# Electrolyser_demo_Dec_2025.net
KiCad netlist of a schematic drawn in EasyEDA
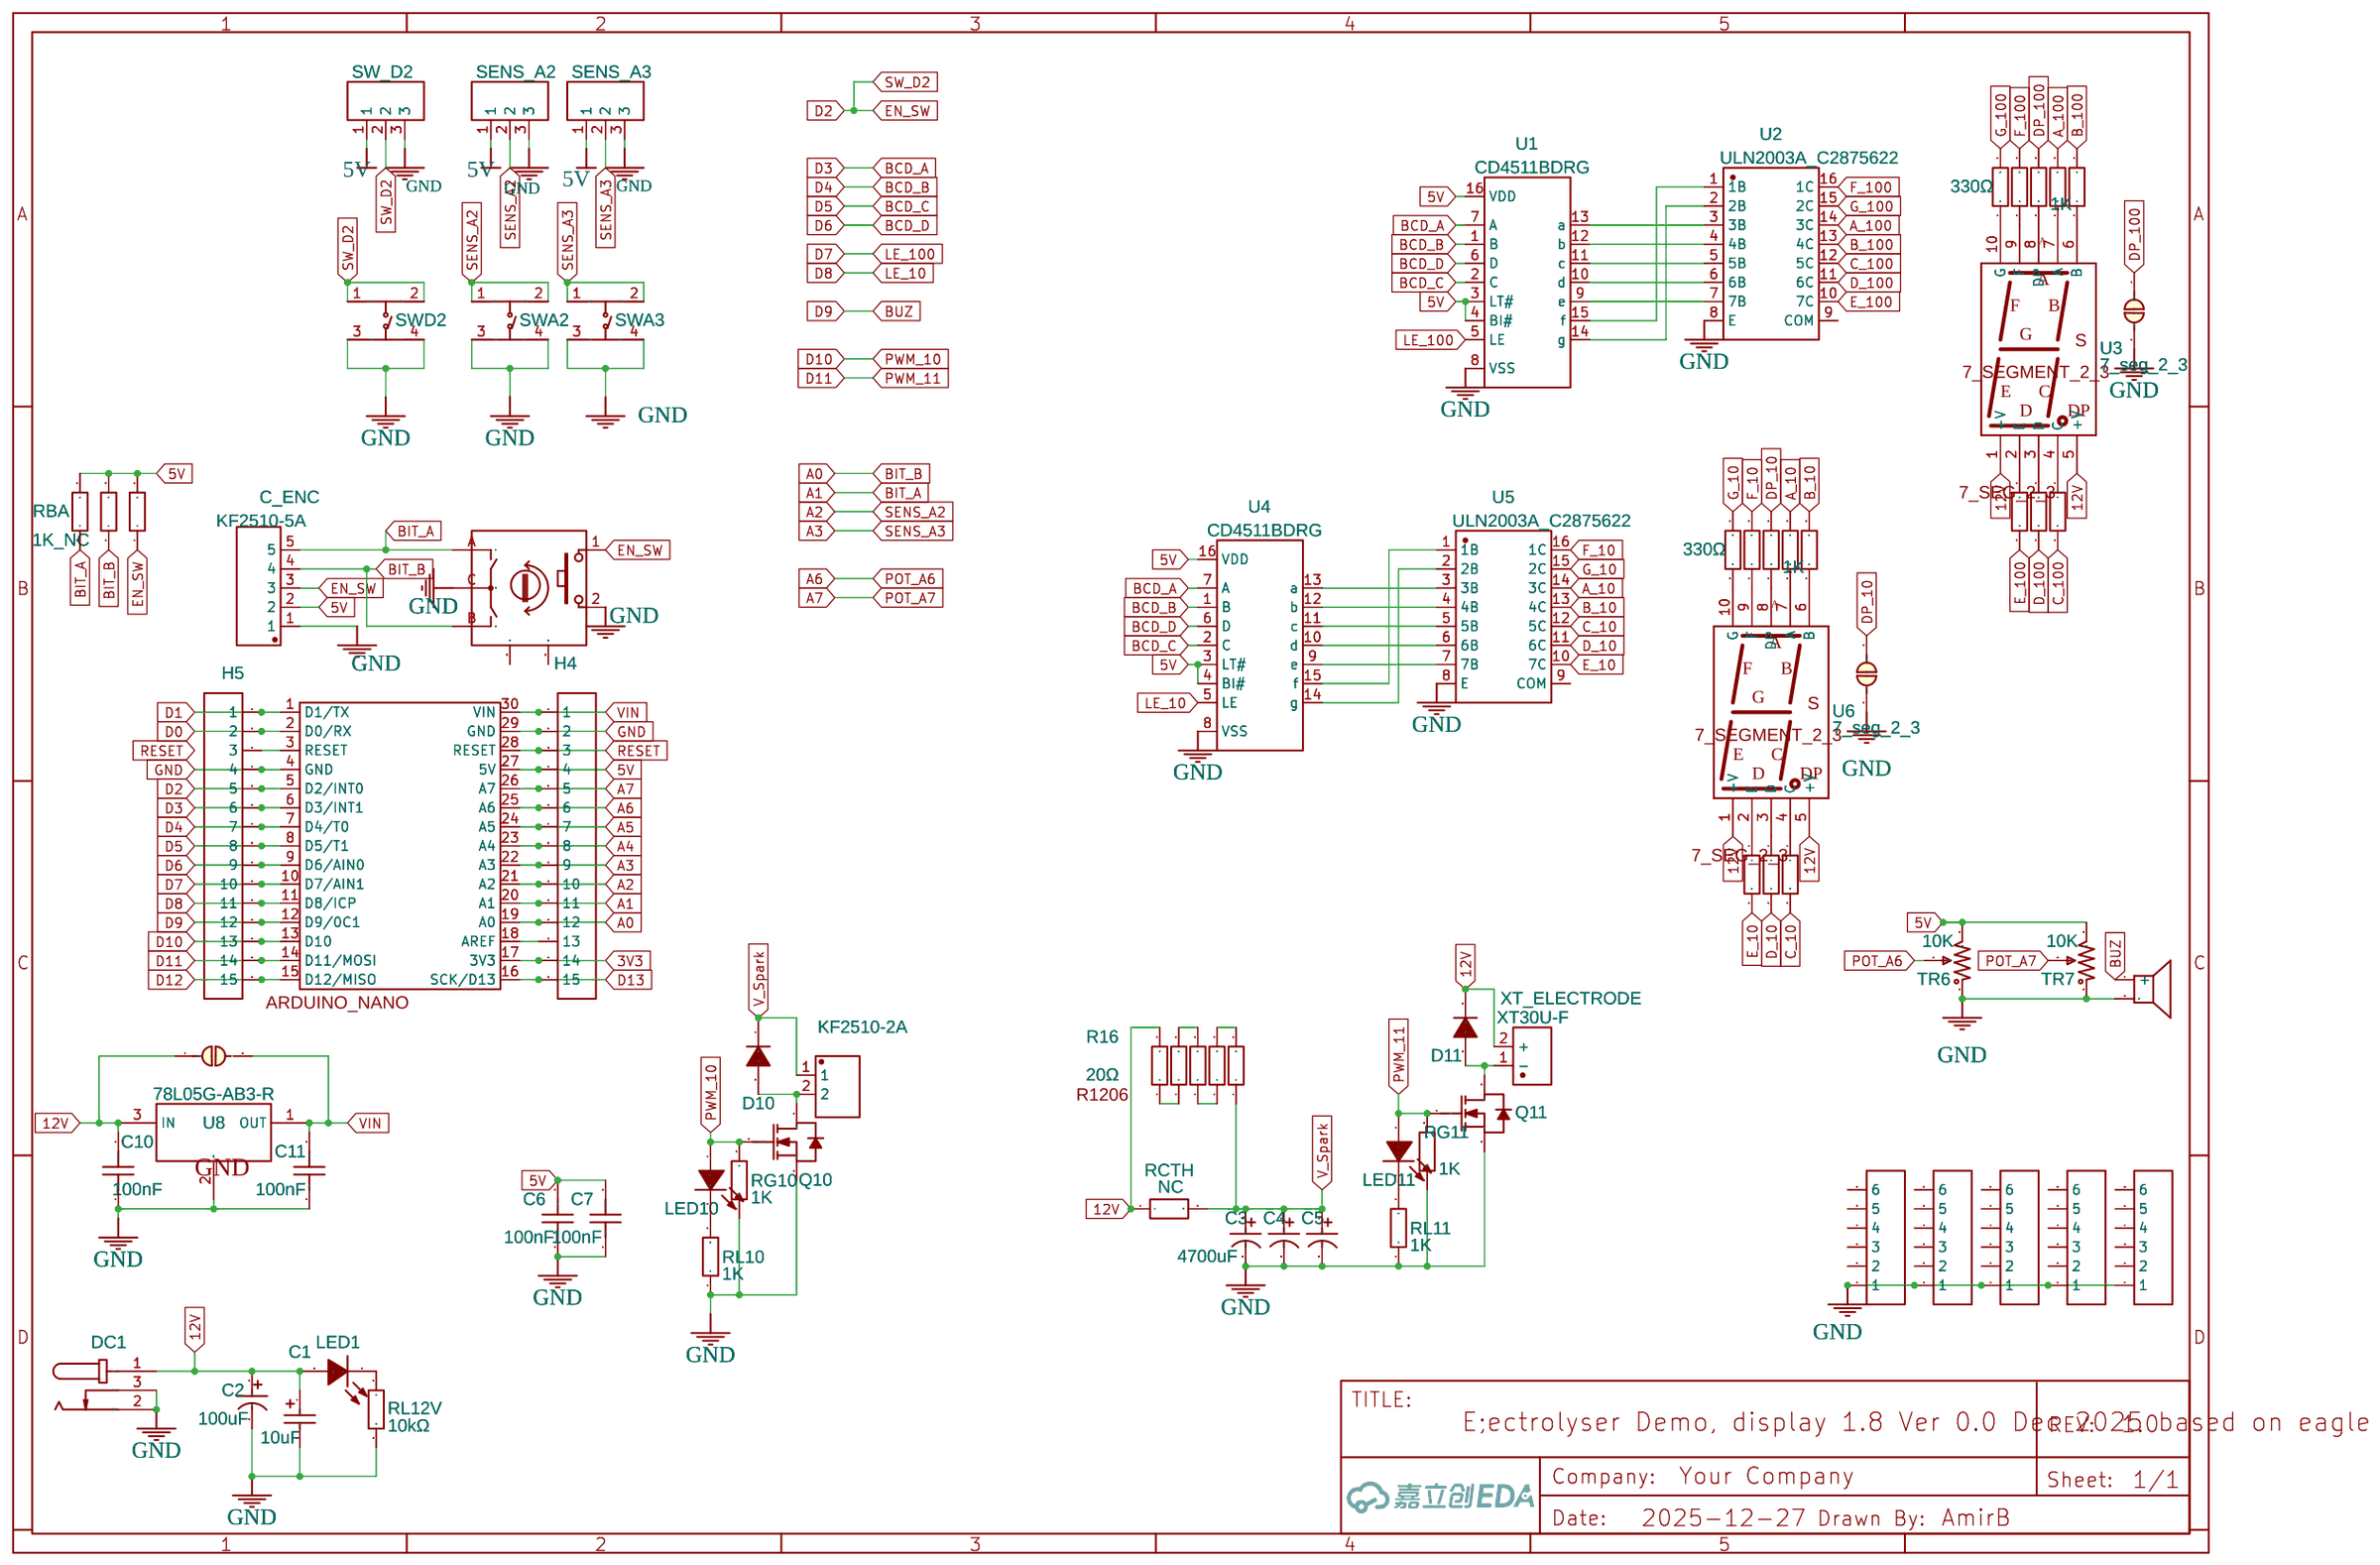
[diagram p0: schematic sheet]

(export (version "E")
  (design (tool "Eeschema 10.0.6"))
  (components
    (comp (ref "BUZZER1")
      (value "BUZZER-12X9")
      (fields (field (name "Manufacturer Part") "buzzer-12X9"))
      (libsource (lib "") (part "BUZZER-12X9"))
    )
    (comp (ref "C1")
      (value "10uF")
      (fields (field (name "Manufacturer Part") "TAJA106K016RNJ") (field (name "Manufacturer") "Kyocera AVX"))
      (libsource (lib "") (part "TAJA106K016RNJ"))
    )
    (comp (ref "C2")
      (value "100uF")
      (fields
        (field (name "Manufacturer Part") "KM107M035E11RR0VH2FP0")
        (field (name "Manufacturer") "CX(承兴)")
      )
      (libsource (lib "") (part "100uF 35V 6.3*11"))
    )
    (comp (ref "C3")
      (value "4700uF")
      (fields
        (field (name "Manufacturer Part") "KM478M025K25RR0VH2FP0")
        (field (name "Manufacturer") "Chengx(承兴)")
      )
      (libsource (lib "") (part "4700uF 25V 16*25V"))
    )
    (comp (ref "C4")
      (value "4700uF")
      (fields
        (field (name "Manufacturer Part") "KM478M025K25RR0VH2FP0")
        (field (name "Manufacturer") "Chengx(承兴)")
      )
      (libsource (lib "") (part "4700uF 25V 16*25V"))
    )
    (comp (ref "C5")
      (value "4700uF")
      (fields
        (field (name "Manufacturer Part") "KM478M025K25RR0VH2FP0")
        (field (name "Manufacturer") "Chengx(承兴)")
      )
      (libsource (lib "") (part "4700uF 25V 16*25V"))
    )
    (comp (ref "C6")
      (value "100nF")
      (fields
        (field (name "Manufacturer Part") "CC0603KRX7R9BB104")
        (field (name "Manufacturer") "YAGEO(国巨)")
      )
      (libsource (lib "") (part "CC0603KRX7R9BB104"))
    )
    (comp (ref "C7")
      (value "100nF")
      (fields
        (field (name "Manufacturer Part") "CC0603KRX7R9BB104")
        (field (name "Manufacturer") "YAGEO(国巨)")
      )
      (libsource (lib "") (part "CC0603KRX7R9BB104"))
    )
    (comp (ref "C10")
      (value "100nF")
      (fields
        (field (name "Manufacturer Part") "CC0603KRX7R9BB104")
        (field (name "Manufacturer") "YAGEO(国巨)")
      )
      (libsource (lib "") (part "CC0603KRX7R9BB104"))
    )
    (comp (ref "C11")
      (value "100nF")
      (fields
        (field (name "Manufacturer Part") "CC0603KRX7R9BB104")
        (field (name "Manufacturer") "YAGEO(国巨)")
      )
      (libsource (lib "") (part "CC0603KRX7R9BB104"))
    )
    (comp (ref "C_ENC")
      (value "KF2510-5A")
      (fields (field (name "Manufacturer Part") "2510-5A") (field (name "Manufacturer") "BOOMELE(博穆精密)"))
      (libsource (lib "") (part "KF2510-5A"))
    )
    (comp (ref "D10")
      (value "SM4007PL")
      (fields (field (name "Manufacturer") "MDD(辰达半导体)"))
      (libsource (lib "") (part "SM4007PL"))
    )
    (comp (ref "D11")
      (value "SM4007PL")
      (fields (field (name "Manufacturer") "MDD(辰达半导体)"))
      (libsource (lib "") (part "SM4007PL"))
    )
    (comp (ref "DC1")
      (value "DC")
      (fields
        (field (name "BOM_Manufacturer Part") "DC005-2.0MM")
        (field (name "BOM_Supplier Part") "C111567")
      )
      (libsource (lib "") (part "DC005-2.0MM"))
    )
    (comp (ref "DP_10") (value "JP") (libsource (lib "") (part "JUMPER-SMT_2_1")))
    (comp (ref "DP_100") (value "JP") (libsource (lib "") (part "JUMPER-SMT_2_1")))
    (comp (ref "H1")
      (value "HDR-F-2.54_1x6")
      (fields (field (name "BOM_Supplier Part") "C40877"))
      (libsource (lib "") (part "HDR-F-2.54_1x6"))
    )
    (comp (ref "H2")
      (value "HDR-F-2.54_1x6")
      (fields (field (name "BOM_Supplier Part") "C40877"))
      (libsource (lib "") (part "HDR-F-2.54_1x6"))
    )
    (comp (ref "H3")
      (value "HDR-F-2.54_1x6")
      (fields (field (name "BOM_Supplier Part") "C40877"))
      (libsource (lib "") (part "HDR-F-2.54_1x6"))
    )
    (comp (ref "H4")
      (value "HDR-F-2.54_1x15")
      (fields (field (name "BOM_Supplier Part") "C124408"))
      (libsource (lib "") (part "HDR-F-2.54_1x15_1"))
    )
    (comp (ref "H5")
      (value "HDR-F-2.54_1x15")
      (fields (field (name "BOM_Supplier Part") "C124408"))
      (libsource (lib "") (part "HDR-F-2.54_1x15"))
    )
    (comp (ref "H6")
      (value "HDR-F-2.54_1x6")
      (fields (field (name "BOM_Supplier Part") "C40877"))
      (libsource (lib "") (part "HDR-F-2.54_1x6"))
    )
    (comp (ref "H11")
      (value "HDR-F-2.54_1x6")
      (fields (field (name "BOM_Supplier Part") "C40877"))
      (libsource (lib "") (part "HDR-F-2.54_1x6"))
    )
    (comp (ref "J_LDO1") (value "JP") (libsource (lib "") (part "JUMPER-SMT_2")))
    (comp (ref "KF_SPARK")
      (value "KF2510-2A")
      (fields (field (name "BOM_Supplier Part") "C27543"))
      (libsource (lib "") (part "KF2510-2A"))
    )
    (comp (ref "LED1")
      (value "KT-0603R")
      (fields (field (name "Manufacturer") "KENTO"))
      (libsource (lib "") (part "KT-0603R"))
    )
    (comp (ref "LED10")
      (value "0603White light_C2290")
      (fields (field (name "Manufacturer Part") "KT-0603W") (field (name "Manufacturer") "KENTO"))
      (libsource (lib "") (part "0603White light_C2290"))
    )
    (comp (ref "LED11")
      (value "0603White light_C2290")
      (fields (field (name "Manufacturer Part") "KT-0603W") (field (name "Manufacturer") "KENTO"))
      (libsource (lib "") (part "0603White light_C2290"))
    )
    (comp (ref "Q10")
      (value "IPD053N06N-DO")
      (fields (field (name "Manufacturer") "DOINGTER(杜因特)"))
      (libsource (lib "") (part "IPD053N06N-DO"))
    )
    (comp (ref "Q11")
      (value "IPD053N06N-DO")
      (fields (field (name "Manufacturer") "DOINGTER(杜因特)"))
      (libsource (lib "") (part "IPD053N06N-DO"))
    )
    (comp (ref "R1")
      (value "330Ω")
      (fields
        (field (name "Manufacturer Part") "0603WAF3300T5E")
        (field (name "Manufacturer") "UNI-ROYAL(厚声)")
      )
      (libsource (lib "") (part "0603WAF3300T5E"))
    )
    (comp (ref "R2")
      (value "330Ω")
      (fields
        (field (name "Manufacturer Part") "0603WAF3300T5E")
        (field (name "Manufacturer") "UNI-ROYAL(厚声)")
      )
      (libsource (lib "") (part "0603WAF3300T5E"))
    )
    (comp (ref "R3")
      (value "330Ω")
      (fields
        (field (name "Manufacturer Part") "0603WAF3300T5E")
        (field (name "Manufacturer") "UNI-ROYAL(厚声)")
      )
      (libsource (lib "") (part "0603WAF3300T5E"))
    )
    (comp (ref "R4")
      (value "330Ω")
      (fields
        (field (name "Manufacturer Part") "0603WAF3300T5E")
        (field (name "Manufacturer") "UNI-ROYAL(厚声)")
      )
      (libsource (lib "") (part "0603WAF3300T5E"))
    )
    (comp (ref "R5")
      (value "330Ω")
      (fields
        (field (name "Manufacturer Part") "0603WAF3300T5E")
        (field (name "Manufacturer") "UNI-ROYAL(厚声)")
      )
      (libsource (lib "") (part "0603WAF3300T5E_1"))
    )
    (comp (ref "R6")
      (value "330Ω")
      (fields
        (field (name "Manufacturer Part") "0603WAF3300T5E")
        (field (name "Manufacturer") "UNI-ROYAL(厚声)")
      )
      (libsource (lib "") (part "0603WAF3300T5E_1"))
    )
    (comp (ref "R7")
      (value "330Ω")
      (fields
        (field (name "Manufacturer Part") "0603WAF3300T5E")
        (field (name "Manufacturer") "UNI-ROYAL(厚声)")
      )
      (libsource (lib "") (part "0603WAF3300T5E_1"))
    )
    (comp (ref "R8")
      (value "330Ω")
      (fields
        (field (name "Manufacturer Part") "0603WAF3300T5E")
        (field (name "Manufacturer") "UNI-ROYAL(厚声)")
      )
      (libsource (lib "") (part "0603WAF3300T5E_1"))
    )
    (comp (ref "R9")
      (value "330Ω")
      (fields
        (field (name "Manufacturer Part") "0603WAF3300T5E")
        (field (name "Manufacturer") "UNI-ROYAL(厚声)")
      )
      (libsource (lib "") (part "0603WAF3300T5E_1"))
    )
    (comp (ref "R10")
      (value "330Ω")
      (fields
        (field (name "Manufacturer Part") "0603WAF3300T5E")
        (field (name "Manufacturer") "UNI-ROYAL(厚声)")
      )
      (libsource (lib "") (part "0603WAF3300T5E_1"))
    )
    (comp (ref "R11")
      (value "330Ω")
      (fields
        (field (name "Manufacturer Part") "0603WAF3300T5E")
        (field (name "Manufacturer") "UNI-ROYAL(厚声)")
      )
      (libsource (lib "") (part "0603WAF3300T5E"))
    )
    (comp (ref "R12")
      (value "330Ω")
      (fields
        (field (name "Manufacturer Part") "0603WAF3300T5E")
        (field (name "Manufacturer") "UNI-ROYAL(厚声)")
      )
      (libsource (lib "") (part "0603WAF3300T5E"))
    )
    (comp (ref "R13")
      (value "330Ω")
      (fields
        (field (name "Manufacturer Part") "0603WAF3300T5E")
        (field (name "Manufacturer") "UNI-ROYAL(厚声)")
      )
      (libsource (lib "") (part "0603WAF3300T5E"))
    )
    (comp (ref "R14")
      (value "330Ω")
      (fields
        (field (name "Manufacturer Part") "0603WAF3300T5E")
        (field (name "Manufacturer") "UNI-ROYAL(厚声)")
      )
      (libsource (lib "") (part "0603WAF3300T5E"))
    )
    (comp (ref "R15")
      (value "20Ω")
      (fields
        (field (name "Manufacturer Part") "1206W4F200JT5E")
        (field (name "Manufacturer") "UNI-ROYAL(厚声)")
      )
      (libsource (lib "") (part "1206W4F200JT5E"))
    )
    (comp (ref "R16")
      (value "20Ω")
      (fields
        (field (name "Manufacturer Part") "1206W4F200JT5E")
        (field (name "Manufacturer") "UNI-ROYAL(厚声)")
      )
      (libsource (lib "") (part "1206W4F200JT5E_1"))
    )
    (comp (ref "R17")
      (value "20Ω")
      (fields
        (field (name "Manufacturer Part") "1206W4F200JT5E")
        (field (name "Manufacturer") "UNI-ROYAL(厚声)")
      )
      (libsource (lib "") (part "1206W4F200JT5E"))
    )
    (comp (ref "R18")
      (value "20Ω")
      (fields
        (field (name "Manufacturer Part") "1206W4F200JT5E")
        (field (name "Manufacturer") "UNI-ROYAL(厚声)")
      )
      (libsource (lib "") (part "1206W4F200JT5E"))
    )
    (comp (ref "R19")
      (value "20Ω")
      (fields
        (field (name "Manufacturer Part") "1206W4F200JT5E")
        (field (name "Manufacturer") "UNI-ROYAL(厚声)")
      )
      (libsource (lib "") (part "1206W4F200JT5E"))
    )
    (comp (ref "RBA")
      (value "1K_NC")
      (fields
        (field (name "BOM_Manufacturer Part") "0603WAF1001T5E")
        (field (name "BOM_Supplier Part") "C21190")
      )
      (libsource (lib "") (part "0603WAF1001T5E_4"))
    )
    (comp (ref "RBB")
      (value "1K_NC")
      (fields
        (field (name "BOM_Manufacturer Part") "0603WAF1001T5E")
        (field (name "BOM_Supplier Part") "C21190")
      )
      (libsource (lib "") (part "0603WAF1001T5E_2"))
    )
    (comp (ref "RCTH") (value "NC") (libsource (lib "") (part "R_AXIAL-0.5_EU")))
    (comp (ref "RES")
      (value "1K_NC")
      (fields
        (field (name "BOM_Manufacturer Part") "0603WAF1001T5E")
        (field (name "BOM_Supplier Part") "C21190")
      )
      (libsource (lib "") (part "0603WAF1001T5E_5"))
    )
    (comp (ref "RG10")
      (value "1K")
      (fields
        (field (name "BOM_Manufacturer Part") "0603WAF1001T5E")
        (field (name "BOM_Supplier Part") "C21190")
      )
      (libsource (lib "") (part "0603WAF1001T5E"))
    )
    (comp (ref "RG11")
      (value "1K")
      (fields
        (field (name "BOM_Manufacturer Part") "0603WAF1001T5E")
        (field (name "BOM_Supplier Part") "C21190")
      )
      (libsource (lib "") (part "0603WAF1001T5E"))
    )
    (comp (ref "RL10")
      (value "1K")
      (fields
        (field (name "BOM_Manufacturer Part") "0603WAF1001T5E")
        (field (name "BOM_Supplier Part") "C21190")
      )
      (libsource (lib "") (part "0603WAF1001T5E_1"))
    )
    (comp (ref "RL11")
      (value "1K")
      (fields
        (field (name "BOM_Manufacturer Part") "0603WAF1001T5E")
        (field (name "BOM_Supplier Part") "C21190")
      )
      (libsource (lib "") (part "0603WAF1001T5E_1"))
    )
    (comp (ref "RL12V")
      (value "10kΩ")
      (fields
        (field (name "BOM_Manufacturer Part") "0603WAF1002T5E")
        (field (name "BOM_Supplier Part") "C25804")
      )
      (libsource (lib "") (part "0603WAF1002T5E"))
    )
    (comp (ref "R_DP_1")
      (value "1K")
      (fields
        (field (name "BOM_Manufacturer Part") "0603WAF1001T5E")
        (field (name "BOM_Supplier Part") "C21190")
      )
      (libsource (lib "") (part "0603WAF1001T5E_3"))
    )
    (comp (ref "R_DP_100")
      (value "1K")
      (fields
        (field (name "BOM_Manufacturer Part") "0603WAF1001T5E")
        (field (name "BOM_Supplier Part") "C21190")
      )
      (libsource (lib "") (part "0603WAF1001T5E_3"))
    )
    (comp (ref "SENS_A2")
      (value "FK2510")
      (fields (field (name "Manufacturer Part") "2510-3A") (field (name "Manufacturer") "BOOMELE(博穆精密)"))
      (libsource (lib "") (part "kf2510_3A_1"))
    )
    (comp (ref "SENS_A3")
      (value "FK2510")
      (fields (field (name "Manufacturer Part") "2510-3A") (field (name "Manufacturer") "BOOMELE(博穆精密)"))
      (libsource (lib "") (part "kf2510_3A_1"))
    )
    (comp (ref "SW1")
      (value "PEC11R-4015F-S0024")
      (fields (field (name "Manufacturer") "BOURNS"))
      (libsource (lib "") (part "PEC11R-4015F-S0024"))
    )
    (comp (ref "SWA2")
      (value "TC-6610-7-160G")
      (fields (field (name "Manufacturer") "HCTL(华灿天禄)"))
      (libsource (lib "") (part "TC-6610-7-160G_1"))
    )
    (comp (ref "SWA3")
      (value "TC-6610-7-160G")
      (fields (field (name "Manufacturer") "HCTL(华灿天禄)"))
      (libsource (lib "") (part "TC-6610-7-160G_1"))
    )
    (comp (ref "SWD2")
      (value "TC-6610-7-160G")
      (fields (field (name "Manufacturer") "HCTL(华灿天禄)"))
      (libsource (lib "") (part "TC-6610-7-160G"))
    )
    (comp (ref "SW_D2")
      (value "FK2510")
      (fields (field (name "Manufacturer Part") "2510-3A") (field (name "Manufacturer") "BOOMELE(博穆精密)"))
      (libsource (lib "") (part "kf2510_3A"))
    )
    (comp (ref "TR6")
      (value "10K")
      (fields (field (name "Manufacturer Part") "3296W-1-202LF") (field (name "Manufacturer") "JIERR(捷而瑞)"))
      (libsource (lib "") (part "3296W-1-202LF_C49190458"))
    )
    (comp (ref "TR7")
      (value "10K")
      (fields (field (name "Manufacturer Part") "3296W-1-202LF") (field (name "Manufacturer") "JIERR(捷而瑞)"))
      (libsource (lib "") (part "3296W-1-202LF_C49190458"))
    )
    (comp (ref "U1")
      (value "CD4511BDRG")
      (fields (field (name "Manufacturer") "HGC(深圳汉芯)"))
      (libsource (lib "") (part "CD4511BDRG"))
    )
    (comp (ref "U2")
      (value "ULN2003A_C2875622")
      (fields (field (name "Manufacturer Part") "ULN2003A") (field (name "Manufacturer") "LANKE(兰科)"))
      (libsource (lib "") (part "ULN2003A_C2875622"))
    )
    (comp (ref "U3") (value "7_seg_2_3") (libsource (lib "") (part "7_seg_2_3_1")))
    (comp (ref "U4")
      (value "CD4511BDRG")
      (fields (field (name "Manufacturer") "HGC(深圳汉芯)"))
      (libsource (lib "") (part "CD4511BDRG"))
    )
    (comp (ref "U5")
      (value "ULN2003A_C2875622")
      (fields (field (name "Manufacturer Part") "ULN2003A") (field (name "Manufacturer") "LANKE(兰科)"))
      (libsource (lib "") (part "ULN2003A_C2875622"))
    )
    (comp (ref "U6") (value "7_seg_2_3") (libsource (lib "") (part "7_seg_2_3")))
    (comp (ref "U8")
      (value "78L05G-AB3-R")
      (fields (field (name "Manufacturer") "UTC(友顺)"))
      (libsource (lib "") (part "78L05G-AB3-R"))
    )
    (comp (ref "UA") (value "Arduino_nano") (libsource (lib "") (part "Arduino_nano")))
    (comp (ref "XT_ELECTRODE")
      (value "XT30U-F")
      (fields (field (name "Manufacturer") "AMASS(艾迈斯)"))
      (libsource (lib "") (part "XT30U-F"))
    )
  )
  (nets
    (net (code "1") (name "3V3") (class "Default")
      (node (ref "H4") (pin "14") (pinfunction "14_14") (pintype "unspecified"))
      (node (ref "UA") (pin "17") (pinfunction "3V3_17") (pintype "unspecified"))
    )
    (net (code "2") (name "5V") (class "Default")
      (node (ref "C6") (pin "2") (pinfunction "2_2") (pintype "unspecified"))
      (node (ref "C7") (pin "2") (pinfunction "2_2") (pintype "unspecified"))
      (node (ref "C_ENC") (pin "2") (pinfunction "2_2") (pintype "unspecified"))
      (node (ref "H4") (pin "4") (pinfunction "4_4") (pintype "unspecified"))
      (node (ref "RBA") (pin "2") (pinfunction "2_2") (pintype "input"))
      (node (ref "RBB") (pin "2") (pinfunction "2_2") (pintype "input"))
      (node (ref "RES") (pin "2") (pinfunction "2_2") (pintype "input"))
      (node (ref "SENS_A2") (pin "1") (pinfunction "1_1") (pintype "unspecified"))
      (node (ref "SENS_A3") (pin "1") (pinfunction "1_1") (pintype "unspecified"))
      (node (ref "SW_D2") (pin "1") (pinfunction "1_1") (pintype "unspecified"))
      (node (ref "TR6") (pin "3") (pinfunction "3_3") (pintype "unspecified"))
      (node (ref "TR7") (pin "3") (pinfunction "3_3") (pintype "unspecified"))
      (node (ref "U1") (pin "16") (pinfunction "VDD_16") (pintype "unspecified"))
      (node (ref "U1") (pin "3") (pinfunction "LT#_3") (pintype "unspecified"))
      (node (ref "U1") (pin "4") (pinfunction "BI#_4") (pintype "unspecified"))
      (node (ref "U4") (pin "16") (pinfunction "VDD_16") (pintype "unspecified"))
      (node (ref "U4") (pin "3") (pinfunction "LT#_3") (pintype "unspecified"))
      (node (ref "U4") (pin "4") (pinfunction "BI#_4") (pintype "unspecified"))
      (node (ref "UA") (pin "27") (pinfunction "5V_27") (pintype "unspecified"))
    )
    (net (code "3") (name "12V") (class "Default")
      (node (ref "C1") (pin "1") (pinfunction "1_1") (pintype "input"))
      (node (ref "C10") (pin "2") (pinfunction "2_2") (pintype "unspecified"))
      (node (ref "C2") (pin "1") (pinfunction "1_1") (pintype "input"))
      (node (ref "D11") (pin "1") (pinfunction "C_1") (pintype "unspecified"))
      (node (ref "DC1") (pin "1") (pinfunction "1_1") (pintype "unspecified"))
      (node (ref "J_LDO1") (pin "1") (pinfunction "1_1") (pintype "bidirectional"))
      (node (ref "LED1") (pin "2") (pinfunction "A_2") (pintype "unspecified"))
      (node (ref "R16") (pin "2") (pinfunction "2_2") (pintype "input"))
      (node (ref "RCTH") (pin "1") (pinfunction "1_1") (pintype "unspecified"))
      (node (ref "U3") (pin "1") (pinfunction "+V_1") (pintype "unspecified"))
      (node (ref "U3") (pin "5") (pinfunction "+V_5") (pintype "unspecified"))
      (node (ref "U6") (pin "1") (pinfunction "+V_1") (pintype "unspecified"))
      (node (ref "U6") (pin "5") (pinfunction "+V_5") (pintype "unspecified"))
      (node (ref "U8") (pin "3") (pinfunction "IN_3") (pintype "passive"))
      (node (ref "XT_ELECTRODE") (pin "2") (pinfunction "+_2") (pintype "unspecified"))
    )
    (net (code "4") (name "A0") (class "Default")
      (node (ref "C_ENC") (pin "4") (pinfunction "4_4") (pintype "unspecified"))
      (node (ref "H4") (pin "12") (pinfunction "12_12") (pintype "unspecified"))
      (node (ref "RBB") (pin "1") (pinfunction "1_1") (pintype "input"))
      (node (ref "SW1") (pin "B") (pinfunction "B_B") (pintype "unspecified"))
      (node (ref "UA") (pin "19") (pinfunction "A0_19") (pintype "unspecified"))
    )
    (net (code "5") (name "A1") (class "Default")
      (node (ref "C_ENC") (pin "5") (pinfunction "5_5") (pintype "unspecified"))
      (node (ref "H4") (pin "11") (pinfunction "11_11") (pintype "unspecified"))
      (node (ref "RBA") (pin "1") (pinfunction "1_1") (pintype "input"))
      (node (ref "SW1") (pin "A") (pinfunction "A_A") (pintype "unspecified"))
      (node (ref "UA") (pin "20") (pinfunction "A1_20") (pintype "unspecified"))
    )
    (net (code "6") (name "A2") (class "Default")
      (node (ref "H4") (pin "10") (pinfunction "10_10") (pintype "unspecified"))
      (node (ref "SENS_A2") (pin "2") (pinfunction "2_2") (pintype "unspecified"))
      (node (ref "SWA2") (pin "1") (pinfunction "1_1") (pintype "unspecified"))
      (node (ref "SWA2") (pin "2") (pinfunction "2_2") (pintype "unspecified"))
      (node (ref "UA") (pin "21") (pinfunction "A2_21") (pintype "unspecified"))
    )
    (net (code "7") (name "A3") (class "Default")
      (node (ref "H4") (pin "9") (pinfunction "9_9") (pintype "unspecified"))
      (node (ref "SENS_A3") (pin "2") (pinfunction "2_2") (pintype "unspecified"))
      (node (ref "SWA3") (pin "1") (pinfunction "1_1") (pintype "unspecified"))
      (node (ref "SWA3") (pin "2") (pinfunction "2_2") (pintype "unspecified"))
      (node (ref "UA") (pin "22") (pinfunction "A3_22") (pintype "unspecified"))
    )
    (net (code "8") (name "A4") (class "Default")
      (node (ref "H4") (pin "8") (pinfunction "8_8") (pintype "unspecified"))
      (node (ref "UA") (pin "23") (pinfunction "A4_23") (pintype "unspecified"))
    )
    (net (code "9") (name "A5") (class "Default")
      (node (ref "H4") (pin "7") (pinfunction "7_7") (pintype "unspecified"))
      (node (ref "UA") (pin "24") (pinfunction "A5_24") (pintype "unspecified"))
    )
    (net (code "10") (name "A6") (class "Default")
      (node (ref "H4") (pin "6") (pinfunction "6_6") (pintype "unspecified"))
      (node (ref "TR6") (pin "2") (pinfunction "2_2") (pintype "unspecified"))
      (node (ref "UA") (pin "25") (pinfunction "A6_25") (pintype "unspecified"))
    )
    (net (code "11") (name "A7") (class "Default")
      (node (ref "H4") (pin "5") (pinfunction "5_5") (pintype "unspecified"))
      (node (ref "TR7") (pin "2") (pinfunction "2_2") (pintype "unspecified"))
      (node (ref "UA") (pin "26") (pinfunction "A7_26") (pintype "unspecified"))
    )
    (net (code "12") (name "A_10") (class "Default")
      (node (ref "R12") (pin "2") (pinfunction "2_2") (pintype "input"))
      (node (ref "U5") (pin "14") (pinfunction "3C_14") (pintype "unspecified"))
    )
    (net (code "13") (name "A_100") (class "Default")
      (node (ref "R3") (pin "2") (pinfunction "2_2") (pintype "input"))
      (node (ref "U2") (pin "14") (pinfunction "3C_14") (pintype "unspecified"))
    )
    (net (code "14") (name "BCD_A") (class "Default")
      (node (ref "H5") (pin "6") (pinfunction "6_6") (pintype "unspecified"))
      (node (ref "U1") (pin "7") (pinfunction "A_7") (pintype "unspecified"))
      (node (ref "U4") (pin "7") (pinfunction "A_7") (pintype "unspecified"))
      (node (ref "UA") (pin "6") (pinfunction "D3/INT1_6") (pintype "unspecified"))
    )
    (net (code "15") (name "BCD_B") (class "Default")
      (node (ref "H5") (pin "7") (pinfunction "7_7") (pintype "unspecified"))
      (node (ref "U1") (pin "1") (pinfunction "B_1") (pintype "unspecified"))
      (node (ref "U4") (pin "1") (pinfunction "B_1") (pintype "unspecified"))
      (node (ref "UA") (pin "7") (pinfunction "D4/T0_7") (pintype "unspecified"))
    )
    (net (code "16") (name "BCD_C") (class "Default")
      (node (ref "H5") (pin "8") (pinfunction "8_8") (pintype "unspecified"))
      (node (ref "U1") (pin "2") (pinfunction "C_2") (pintype "unspecified"))
      (node (ref "U4") (pin "2") (pinfunction "C_2") (pintype "unspecified"))
      (node (ref "UA") (pin "8") (pinfunction "D5/T1_8") (pintype "unspecified"))
    )
    (net (code "17") (name "BCD_D") (class "Default")
      (node (ref "H5") (pin "9") (pinfunction "9_9") (pintype "unspecified"))
      (node (ref "U1") (pin "6") (pinfunction "D_6") (pintype "unspecified"))
      (node (ref "U4") (pin "6") (pinfunction "D_6") (pintype "unspecified"))
      (node (ref "UA") (pin "9") (pinfunction "D6/AIN0_9") (pintype "unspecified"))
    )
    (net (code "18") (name "BUZ") (class "Default")
      (node (ref "BUZZER1") (pin "1") (pinfunction "+_1") (pintype "unspecified"))
      (node (ref "H5") (pin "12") (pinfunction "12_12") (pintype "unspecified"))
      (node (ref "UA") (pin "12") (pinfunction "D9/0C1_12") (pintype "unspecified"))
    )
    (net (code "19") (name "B_10") (class "Default")
      (node (ref "R11") (pin "2") (pinfunction "2_2") (pintype "input"))
      (node (ref "U5") (pin "13") (pinfunction "4C_13") (pintype "unspecified"))
    )
    (net (code "20") (name "B_100") (class "Default")
      (node (ref "R4") (pin "2") (pinfunction "2_2") (pintype "input"))
      (node (ref "U2") (pin "13") (pinfunction "4C_13") (pintype "unspecified"))
    )
    (net (code "21") (name "C_10") (class "Default")
      (node (ref "R8") (pin "2") (pinfunction "2_2") (pintype "input"))
      (node (ref "U5") (pin "12") (pinfunction "5C_12") (pintype "unspecified"))
    )
    (net (code "22") (name "C_100") (class "Default")
      (node (ref "R7") (pin "2") (pinfunction "2_2") (pintype "input"))
      (node (ref "U2") (pin "12") (pinfunction "5C_12") (pintype "unspecified"))
    )
    (net (code "23") (name "D0") (class "Default")
      (node (ref "H5") (pin "2") (pinfunction "2_2") (pintype "unspecified"))
      (node (ref "UA") (pin "2") (pinfunction "D0/RX_2") (pintype "unspecified"))
    )
    (net (code "24") (name "D1") (class "Default")
      (node (ref "H5") (pin "1") (pinfunction "1_1") (pintype "unspecified"))
      (node (ref "UA") (pin "1") (pinfunction "D1/TX_1") (pintype "unspecified"))
    )
    (net (code "25") (name "D2") (class "Default")
      (node (ref "C_ENC") (pin "3") (pinfunction "3_3") (pintype "unspecified"))
      (node (ref "H5") (pin "5") (pinfunction "5_5") (pintype "unspecified"))
      (node (ref "RES") (pin "1") (pinfunction "1_1") (pintype "input"))
      (node (ref "SW1") (pin "1") (pinfunction "1_1") (pintype "unspecified"))
      (node (ref "SWD2") (pin "1") (pinfunction "1_1") (pintype "unspecified"))
      (node (ref "SWD2") (pin "2") (pinfunction "2_2") (pintype "unspecified"))
      (node (ref "SW_D2") (pin "2") (pinfunction "2_2") (pintype "unspecified"))
      (node (ref "UA") (pin "5") (pinfunction "D2/INT0_5") (pintype "unspecified"))
    )
    (net (code "26") (name "D7") (class "Default")
      (node (ref "H5") (pin "10") (pinfunction "10_10") (pintype "unspecified"))
      (node (ref "U1") (pin "5") (pinfunction "LE_5") (pintype "unspecified"))
      (node (ref "UA") (pin "10") (pinfunction "D7/AIN1_10") (pintype "unspecified"))
    )
    (net (code "27") (name "D8") (class "Default")
      (node (ref "H5") (pin "11") (pinfunction "11_11") (pintype "unspecified"))
      (node (ref "U4") (pin "5") (pinfunction "LE_5") (pintype "unspecified"))
      (node (ref "UA") (pin "11") (pinfunction "D8/ICP_11") (pintype "unspecified"))
    )
    (net (code "28") (name "D10") (class "Default")
      (node (ref "H5") (pin "13") (pinfunction "13_13") (pintype "unspecified"))
      (node (ref "LED10") (pin "1") (pinfunction "A_1") (pintype "unspecified"))
      (node (ref "Q10") (pin "1") (pinfunction "G_1") (pintype "unspecified"))
      (node (ref "RG10") (pin "2") (pinfunction "2_2") (pintype "input"))
      (node (ref "UA") (pin "13") (pinfunction "D10_13") (pintype "unspecified"))
    )
    (net (code "29") (name "D11") (class "Default")
      (node (ref "H5") (pin "14") (pinfunction "14_14") (pintype "unspecified"))
      (node (ref "LED11") (pin "1") (pinfunction "A_1") (pintype "unspecified"))
      (node (ref "Q11") (pin "1") (pinfunction "G_1") (pintype "unspecified"))
      (node (ref "RG11") (pin "2") (pinfunction "2_2") (pintype "input"))
      (node (ref "UA") (pin "14") (pinfunction "D11/MOSI_14") (pintype "unspecified"))
    )
    (net (code "30") (name "D12") (class "Default")
      (node (ref "H5") (pin "15") (pinfunction "15_15") (pintype "unspecified"))
      (node (ref "UA") (pin "15") (pinfunction "D12/MISO_15") (pintype "unspecified"))
    )
    (net (code "31") (name "D13") (class "Default")
      (node (ref "H4") (pin "15") (pinfunction "15_15") (pintype "unspecified"))
      (node (ref "UA") (pin "16") (pinfunction "SCK/D13_16") (pintype "unspecified"))
    )
    (net (code "32") (name "DP_10") (class "Default")
      (node (ref "DP_10") (pin "1") (pinfunction "1_1") (pintype "bidirectional"))
      (node (ref "R_DP_1") (pin "2") (pinfunction "2_2") (pintype "input"))
    )
    (net (code "33") (name "DP_100") (class "Default")
      (node (ref "DP_100") (pin "1") (pinfunction "1_1") (pintype "bidirectional"))
      (node (ref "R_DP_100") (pin "2") (pinfunction "2_2") (pintype "input"))
    )
    (net (code "34") (name "D_10") (class "Default")
      (node (ref "R9") (pin "2") (pinfunction "2_2") (pintype "input"))
      (node (ref "U5") (pin "11") (pinfunction "6C_11") (pintype "unspecified"))
    )
    (net (code "35") (name "D_100") (class "Default")
      (node (ref "R6") (pin "2") (pinfunction "2_2") (pintype "input"))
      (node (ref "U2") (pin "11") (pinfunction "6C_11") (pintype "unspecified"))
    )
    (net (code "36") (name "E_10") (class "Default")
      (node (ref "R10") (pin "2") (pinfunction "2_2") (pintype "input"))
      (node (ref "U5") (pin "10") (pinfunction "7C_10") (pintype "unspecified"))
    )
    (net (code "37") (name "E_100") (class "Default")
      (node (ref "R5") (pin "2") (pinfunction "2_2") (pintype "input"))
      (node (ref "U2") (pin "10") (pinfunction "7C_10") (pintype "unspecified"))
    )
    (net (code "38") (name "F_10") (class "Default")
      (node (ref "R13") (pin "2") (pinfunction "2_2") (pintype "input"))
      (node (ref "U5") (pin "16") (pinfunction "1C_16") (pintype "unspecified"))
    )
    (net (code "39") (name "F_100") (class "Default")
      (node (ref "R2") (pin "2") (pinfunction "2_2") (pintype "input"))
      (node (ref "U2") (pin "16") (pinfunction "1C_16") (pintype "unspecified"))
    )
    (net (code "40") (name "GND") (class "Default")
      (node (ref "BUZZER1") (pin "2") (pinfunction "2_2") (pintype "unspecified"))
      (node (ref "C1") (pin "2") (pinfunction "2_2") (pintype "input"))
      (node (ref "C10") (pin "1") (pinfunction "1_1") (pintype "unspecified"))
      (node (ref "C11") (pin "1") (pinfunction "1_1") (pintype "unspecified"))
      (node (ref "C2") (pin "2") (pinfunction "2_2") (pintype "input"))
      (node (ref "C3") (pin "2") (pinfunction "2_2") (pintype "input"))
      (node (ref "C4") (pin "2") (pinfunction "2_2") (pintype "input"))
      (node (ref "C5") (pin "2") (pinfunction "2_2") (pintype "input"))
      (node (ref "C6") (pin "1") (pinfunction "1_1") (pintype "unspecified"))
      (node (ref "C7") (pin "1") (pinfunction "1_1") (pintype "unspecified"))
      (node (ref "C_ENC") (pin "1") (pinfunction "1_1") (pintype "unspecified"))
      (node (ref "DC1") (pin "2") (pinfunction "2_2") (pintype "unspecified"))
      (node (ref "DC1") (pin "3") (pinfunction "3_3") (pintype "unspecified"))
      (node (ref "DP_10") (pin "2") (pinfunction "2_2") (pintype "bidirectional"))
      (node (ref "DP_100") (pin "2") (pinfunction "2_2") (pintype "bidirectional"))
      (node (ref "H1") (pin "1") (pinfunction "1_1") (pintype "input"))
      (node (ref "H11") (pin "1") (pinfunction "1_1") (pintype "input"))
      (node (ref "H2") (pin "1") (pinfunction "1_1") (pintype "input"))
      (node (ref "H3") (pin "1") (pinfunction "1_1") (pintype "input"))
      (node (ref "H4") (pin "2") (pinfunction "2_2") (pintype "unspecified"))
      (node (ref "H5") (pin "4") (pinfunction "4_4") (pintype "unspecified"))
      (node (ref "H6") (pin "1") (pinfunction "1_1") (pintype "input"))
      (node (ref "Q10") (pin "3") (pinfunction "S_3") (pintype "unspecified"))
      (node (ref "Q11") (pin "3") (pinfunction "S_3") (pintype "unspecified"))
      (node (ref "RG10") (pin "1") (pinfunction "1_1") (pintype "input"))
      (node (ref "RG11") (pin "1") (pinfunction "1_1") (pintype "input"))
      (node (ref "RL10") (pin "1") (pinfunction "1_1") (pintype "input"))
      (node (ref "RL11") (pin "1") (pinfunction "1_1") (pintype "input"))
      (node (ref "RL12V") (pin "2") (pinfunction "2_2") (pintype "input"))
      (node (ref "SENS_A2") (pin "3") (pinfunction "3_3") (pintype "unspecified"))
      (node (ref "SENS_A3") (pin "3") (pinfunction "3_3") (pintype "unspecified"))
      (node (ref "SW1") (pin "2") (pinfunction "2_2") (pintype "unspecified"))
      (node (ref "SW1") (pin "C") (pinfunction "C_C") (pintype "unspecified"))
      (node (ref "SWA2") (pin "3") (pinfunction "3_3") (pintype "unspecified"))
      (node (ref "SWA2") (pin "4") (pinfunction "4_4") (pintype "unspecified"))
      (node (ref "SWA3") (pin "3") (pinfunction "3_3") (pintype "unspecified"))
      (node (ref "SWA3") (pin "4") (pinfunction "4_4") (pintype "unspecified"))
      (node (ref "SWD2") (pin "3") (pinfunction "3_3") (pintype "unspecified"))
      (node (ref "SWD2") (pin "4") (pinfunction "4_4") (pintype "unspecified"))
      (node (ref "SW_D2") (pin "3") (pinfunction "3_3") (pintype "unspecified"))
      (node (ref "TR6") (pin "1") (pinfunction "1_1") (pintype "unspecified"))
      (node (ref "TR7") (pin "1") (pinfunction "1_1") (pintype "unspecified"))
      (node (ref "U1") (pin "8") (pinfunction "VSS_8") (pintype "unspecified"))
      (node (ref "U2") (pin "8") (pinfunction "E_8") (pintype "unspecified"))
      (node (ref "U4") (pin "8") (pinfunction "VSS_8") (pintype "unspecified"))
      (node (ref "U5") (pin "8") (pinfunction "E_8") (pintype "unspecified"))
      (node (ref "U8") (pin "2") (pinfunction "GND_2") (pintype "passive"))
      (node (ref "UA") (pin "29") (pinfunction "GND_29") (pintype "unspecified"))
      (node (ref "UA") (pin "4") (pinfunction "GND_4") (pintype "unspecified"))
    )
    (net (code "41") (name "G_10") (class "Default")
      (node (ref "R14") (pin "2") (pinfunction "2_2") (pintype "input"))
      (node (ref "U5") (pin "15") (pinfunction "2C_15") (pintype "unspecified"))
    )
    (net (code "42") (name "G_100") (class "Default")
      (node (ref "R1") (pin "2") (pinfunction "2_2") (pintype "input"))
      (node (ref "U2") (pin "15") (pinfunction "2C_15") (pintype "unspecified"))
    )
    (net (code "43") (name "Net-(D10-A)") (class "Default")
      (node (ref "D10") (pin "2") (pinfunction "A_2") (pintype "unspecified"))
      (node (ref "KF_SPARK") (pin "2") (pinfunction "2_2") (pintype "unspecified"))
      (node (ref "Q10") (pin "2") (pinfunction "D_2") (pintype "unspecified"))
    )
    (net (code "44") (name "Net-(D11-A)") (class "Default")
      (node (ref "D11") (pin "2") (pinfunction "A_2") (pintype "unspecified"))
      (node (ref "Q11") (pin "2") (pinfunction "D_2") (pintype "unspecified"))
      (node (ref "XT_ELECTRODE") (pin "1") (pinfunction "-_1") (pintype "unspecified"))
    )
    (net (code "45") (name "Net-(H5-Pad3)") (class "Default")
      (node (ref "H5") (pin "3") (pinfunction "3_3") (pintype "unspecified"))
      (node (ref "UA") (pin "3") (pinfunction "RESET_3") (pintype "unspecified"))
    )
    (net (code "46") (name "Net-(LED1-K)") (class "Default")
      (node (ref "LED1") (pin "1") (pinfunction "K_1") (pintype "unspecified"))
      (node (ref "RL12V") (pin "1") (pinfunction "1_1") (pintype "input"))
    )
    (net (code "47") (name "Net-(LED10-K)") (class "Default")
      (node (ref "LED10") (pin "2") (pinfunction "K_2") (pintype "unspecified"))
      (node (ref "RL10") (pin "2") (pinfunction "2_2") (pintype "input"))
    )
    (net (code "48") (name "Net-(LED11-K)") (class "Default")
      (node (ref "LED11") (pin "2") (pinfunction "K_2") (pintype "unspecified"))
      (node (ref "RL11") (pin "2") (pinfunction "2_2") (pintype "input"))
    )
    (net (code "49") (name "Net-(R15-Pad1)") (class "Default")
      (node (ref "R15") (pin "1") (pinfunction "1_1") (pintype "input"))
      (node (ref "R16") (pin "1") (pinfunction "1_1") (pintype "input"))
    )
    (net (code "50") (name "Net-(R15-Pad2)") (class "Default")
      (node (ref "R15") (pin "2") (pinfunction "2_2") (pintype "input"))
      (node (ref "R17") (pin "2") (pinfunction "2_2") (pintype "input"))
    )
    (net (code "51") (name "Net-(R17-Pad1)") (class "Default")
      (node (ref "R17") (pin "1") (pinfunction "1_1") (pintype "input"))
      (node (ref "R18") (pin "1") (pinfunction "1_1") (pintype "input"))
    )
    (net (code "52") (name "Net-(R18-Pad2)") (class "Default")
      (node (ref "R18") (pin "2") (pinfunction "2_2") (pintype "input"))
      (node (ref "R19") (pin "2") (pinfunction "2_2") (pintype "input"))
    )
    (net (code "53") (name "Net-(U1-a)") (class "Default")
      (node (ref "U1") (pin "13") (pinfunction "a_13") (pintype "unspecified"))
      (node (ref "U2") (pin "3") (pinfunction "3B_3") (pintype "unspecified"))
    )
    (net (code "54") (name "Net-(U1-b)") (class "Default")
      (node (ref "U1") (pin "12") (pinfunction "b_12") (pintype "unspecified"))
      (node (ref "U2") (pin "4") (pinfunction "4B_4") (pintype "unspecified"))
    )
    (net (code "55") (name "Net-(U1-c)") (class "Default")
      (node (ref "U1") (pin "11") (pinfunction "c_11") (pintype "unspecified"))
      (node (ref "U2") (pin "5") (pinfunction "5B_5") (pintype "unspecified"))
    )
    (net (code "56") (name "Net-(U1-d)") (class "Default")
      (node (ref "U1") (pin "10") (pinfunction "d_10") (pintype "unspecified"))
      (node (ref "U2") (pin "6") (pinfunction "6B_6") (pintype "unspecified"))
    )
    (net (code "57") (name "Net-(U1-e)") (class "Default")
      (node (ref "U1") (pin "9") (pinfunction "e_9") (pintype "unspecified"))
      (node (ref "U2") (pin "7") (pinfunction "7B_7") (pintype "unspecified"))
    )
    (net (code "58") (name "Net-(U1-f)") (class "Default")
      (node (ref "U1") (pin "15") (pinfunction "f_15") (pintype "unspecified"))
      (node (ref "U2") (pin "1") (pinfunction "1B_1") (pintype "unspecified"))
    )
    (net (code "59") (name "Net-(U1-g)") (class "Default")
      (node (ref "U1") (pin "14") (pinfunction "g_14") (pintype "unspecified"))
      (node (ref "U2") (pin "2") (pinfunction "2B_2") (pintype "unspecified"))
    )
    (net (code "60") (name "Net-(U3-A)") (class "Default")
      (node (ref "R3") (pin "1") (pinfunction "1_1") (pintype "input"))
      (node (ref "U3") (pin "7") (pinfunction "A_7") (pintype "unspecified"))
    )
    (net (code "61") (name "Net-(U3-B)") (class "Default")
      (node (ref "R4") (pin "1") (pinfunction "1_1") (pintype "input"))
      (node (ref "U3") (pin "6") (pinfunction "B_6") (pintype "unspecified"))
    )
    (net (code "62") (name "Net-(U3-C)") (class "Default")
      (node (ref "R7") (pin "1") (pinfunction "1_1") (pintype "input"))
      (node (ref "U3") (pin "4") (pinfunction "C_4") (pintype "unspecified"))
    )
    (net (code "63") (name "Net-(U3-D)") (class "Default")
      (node (ref "R6") (pin "1") (pinfunction "1_1") (pintype "input"))
      (node (ref "U3") (pin "3") (pinfunction "D_3") (pintype "unspecified"))
    )
    (net (code "64") (name "Net-(U3-DP)") (class "Default")
      (node (ref "R_DP_100") (pin "1") (pinfunction "1_1") (pintype "input"))
      (node (ref "U3") (pin "8") (pinfunction "DP_8") (pintype "unspecified"))
    )
    (net (code "65") (name "Net-(U3-E)") (class "Default")
      (node (ref "R5") (pin "1") (pinfunction "1_1") (pintype "input"))
      (node (ref "U3") (pin "2") (pinfunction "E_2") (pintype "unspecified"))
    )
    (net (code "66") (name "Net-(U3-F)") (class "Default")
      (node (ref "R2") (pin "1") (pinfunction "1_1") (pintype "input"))
      (node (ref "U3") (pin "9") (pinfunction "F_9") (pintype "unspecified"))
    )
    (net (code "67") (name "Net-(U3-G)") (class "Default")
      (node (ref "R1") (pin "1") (pinfunction "1_1") (pintype "input"))
      (node (ref "U3") (pin "10") (pinfunction "G_10") (pintype "unspecified"))
    )
    (net (code "68") (name "Net-(U4-a)") (class "Default")
      (node (ref "U4") (pin "13") (pinfunction "a_13") (pintype "unspecified"))
      (node (ref "U5") (pin "3") (pinfunction "3B_3") (pintype "unspecified"))
    )
    (net (code "69") (name "Net-(U4-b)") (class "Default")
      (node (ref "U4") (pin "12") (pinfunction "b_12") (pintype "unspecified"))
      (node (ref "U5") (pin "4") (pinfunction "4B_4") (pintype "unspecified"))
    )
    (net (code "70") (name "Net-(U4-c)") (class "Default")
      (node (ref "U4") (pin "11") (pinfunction "c_11") (pintype "unspecified"))
      (node (ref "U5") (pin "5") (pinfunction "5B_5") (pintype "unspecified"))
    )
    (net (code "71") (name "Net-(U4-d)") (class "Default")
      (node (ref "U4") (pin "10") (pinfunction "d_10") (pintype "unspecified"))
      (node (ref "U5") (pin "6") (pinfunction "6B_6") (pintype "unspecified"))
    )
    (net (code "72") (name "Net-(U4-e)") (class "Default")
      (node (ref "U4") (pin "9") (pinfunction "e_9") (pintype "unspecified"))
      (node (ref "U5") (pin "7") (pinfunction "7B_7") (pintype "unspecified"))
    )
    (net (code "73") (name "Net-(U4-f)") (class "Default")
      (node (ref "U4") (pin "15") (pinfunction "f_15") (pintype "unspecified"))
      (node (ref "U5") (pin "1") (pinfunction "1B_1") (pintype "unspecified"))
    )
    (net (code "74") (name "Net-(U4-g)") (class "Default")
      (node (ref "U4") (pin "14") (pinfunction "g_14") (pintype "unspecified"))
      (node (ref "U5") (pin "2") (pinfunction "2B_2") (pintype "unspecified"))
    )
    (net (code "75") (name "Net-(U6-A)") (class "Default")
      (node (ref "R12") (pin "1") (pinfunction "1_1") (pintype "input"))
      (node (ref "U6") (pin "7") (pinfunction "A_7") (pintype "unspecified"))
    )
    (net (code "76") (name "Net-(U6-B)") (class "Default")
      (node (ref "R11") (pin "1") (pinfunction "1_1") (pintype "input"))
      (node (ref "U6") (pin "6") (pinfunction "B_6") (pintype "unspecified"))
    )
    (net (code "77") (name "Net-(U6-C)") (class "Default")
      (node (ref "R8") (pin "1") (pinfunction "1_1") (pintype "input"))
      (node (ref "U6") (pin "4") (pinfunction "C_4") (pintype "unspecified"))
    )
    (net (code "78") (name "Net-(U6-D)") (class "Default")
      (node (ref "R9") (pin "1") (pinfunction "1_1") (pintype "input"))
      (node (ref "U6") (pin "3") (pinfunction "D_3") (pintype "unspecified"))
    )
    (net (code "79") (name "Net-(U6-DP)") (class "Default")
      (node (ref "R_DP_1") (pin "1") (pinfunction "1_1") (pintype "input"))
      (node (ref "U6") (pin "8") (pinfunction "DP_8") (pintype "unspecified"))
    )
    (net (code "80") (name "Net-(U6-E)") (class "Default")
      (node (ref "R10") (pin "1") (pinfunction "1_1") (pintype "input"))
      (node (ref "U6") (pin "2") (pinfunction "E_2") (pintype "unspecified"))
    )
    (net (code "81") (name "Net-(U6-F)") (class "Default")
      (node (ref "R13") (pin "1") (pinfunction "1_1") (pintype "input"))
      (node (ref "U6") (pin "9") (pinfunction "F_9") (pintype "unspecified"))
    )
    (net (code "82") (name "Net-(U6-G)") (class "Default")
      (node (ref "R14") (pin "1") (pinfunction "1_1") (pintype "input"))
      (node (ref "U6") (pin "10") (pinfunction "G_10") (pintype "unspecified"))
    )
    (net (code "83") (name "Net-(UA-AREF)") (class "Default")
      (node (ref "H4") (pin "13") (pinfunction "13_13") (pintype "unspecified"))
      (node (ref "UA") (pin "18") (pinfunction "AREF_18") (pintype "unspecified"))
    )
    (net (code "84") (name "RESET") (class "Default")
      (node (ref "H4") (pin "3") (pinfunction "3_3") (pintype "unspecified"))
      (node (ref "UA") (pin "28") (pinfunction "RESET_28") (pintype "unspecified"))
    )
    (net (code "85") (name "VIN") (class "Default")
      (node (ref "C11") (pin "2") (pinfunction "2_2") (pintype "unspecified"))
      (node (ref "H4") (pin "1") (pinfunction "1_1") (pintype "unspecified"))
      (node (ref "J_LDO1") (pin "2") (pinfunction "2_2") (pintype "bidirectional"))
      (node (ref "U8") (pin "1") (pinfunction "OUT_1") (pintype "passive"))
      (node (ref "UA") (pin "30") (pinfunction "VIN_30") (pintype "unspecified"))
    )
    (net (code "86") (name "V_Spark") (class "Default")
      (node (ref "C3") (pin "1") (pinfunction "1_1") (pintype "input"))
      (node (ref "C4") (pin "1") (pinfunction "1_1") (pintype "input"))
      (node (ref "C5") (pin "1") (pinfunction "1_1") (pintype "input"))
      (node (ref "D10") (pin "1") (pinfunction "C_1") (pintype "unspecified"))
      (node (ref "KF_SPARK") (pin "1") (pinfunction "1_1") (pintype "unspecified"))
      (node (ref "R19") (pin "1") (pinfunction "1_1") (pintype "input"))
      (node (ref "RCTH") (pin "2") (pinfunction "2_2") (pintype "unspecified"))
    )
    (net (code "87") (name "unconnected-(H1-Pad2)") (class "Default")
      (node (ref "H1") (pin "2") (pinfunction "2_2") (pintype "input"))
    )
    (net (code "88") (name "unconnected-(H1-Pad3)") (class "Default")
      (node (ref "H1") (pin "3") (pinfunction "3_3") (pintype "input"))
    )
    (net (code "89") (name "unconnected-(H1-Pad4)") (class "Default")
      (node (ref "H1") (pin "4") (pinfunction "4_4") (pintype "input"))
    )
    (net (code "90") (name "unconnected-(H1-Pad5)") (class "Default")
      (node (ref "H1") (pin "5") (pinfunction "5_5") (pintype "input"))
    )
    (net (code "91") (name "unconnected-(H1-Pad6)") (class "Default")
      (node (ref "H1") (pin "6") (pinfunction "6_6") (pintype "input"))
    )
    (net (code "92") (name "unconnected-(H2-Pad2)") (class "Default")
      (node (ref "H2") (pin "2") (pinfunction "2_2") (pintype "input"))
    )
    (net (code "93") (name "unconnected-(H2-Pad3)") (class "Default")
      (node (ref "H2") (pin "3") (pinfunction "3_3") (pintype "input"))
    )
    (net (code "94") (name "unconnected-(H2-Pad4)") (class "Default")
      (node (ref "H2") (pin "4") (pinfunction "4_4") (pintype "input"))
    )
    (net (code "95") (name "unconnected-(H2-Pad5)") (class "Default")
      (node (ref "H2") (pin "5") (pinfunction "5_5") (pintype "input"))
    )
    (net (code "96") (name "unconnected-(H2-Pad6)") (class "Default")
      (node (ref "H2") (pin "6") (pinfunction "6_6") (pintype "input"))
    )
    (net (code "97") (name "unconnected-(H3-Pad2)") (class "Default")
      (node (ref "H3") (pin "2") (pinfunction "2_2") (pintype "input"))
    )
    (net (code "98") (name "unconnected-(H3-Pad3)") (class "Default")
      (node (ref "H3") (pin "3") (pinfunction "3_3") (pintype "input"))
    )
    (net (code "99") (name "unconnected-(H3-Pad4)") (class "Default")
      (node (ref "H3") (pin "4") (pinfunction "4_4") (pintype "input"))
    )
    (net (code "100") (name "unconnected-(H3-Pad5)") (class "Default")
      (node (ref "H3") (pin "5") (pinfunction "5_5") (pintype "input"))
    )
    (net (code "101") (name "unconnected-(H3-Pad6)") (class "Default")
      (node (ref "H3") (pin "6") (pinfunction "6_6") (pintype "input"))
    )
    (net (code "102") (name "unconnected-(H6-Pad2)") (class "Default")
      (node (ref "H6") (pin "2") (pinfunction "2_2") (pintype "input"))
    )
    (net (code "103") (name "unconnected-(H6-Pad3)") (class "Default")
      (node (ref "H6") (pin "3") (pinfunction "3_3") (pintype "input"))
    )
    (net (code "104") (name "unconnected-(H6-Pad4)") (class "Default")
      (node (ref "H6") (pin "4") (pinfunction "4_4") (pintype "input"))
    )
    (net (code "105") (name "unconnected-(H6-Pad5)") (class "Default")
      (node (ref "H6") (pin "5") (pinfunction "5_5") (pintype "input"))
    )
    (net (code "106") (name "unconnected-(H6-Pad6)") (class "Default")
      (node (ref "H6") (pin "6") (pinfunction "6_6") (pintype "input"))
    )
    (net (code "107") (name "unconnected-(H11-Pad2)") (class "Default")
      (node (ref "H11") (pin "2") (pinfunction "2_2") (pintype "input"))
    )
    (net (code "108") (name "unconnected-(H11-Pad3)") (class "Default")
      (node (ref "H11") (pin "3") (pinfunction "3_3") (pintype "input"))
    )
    (net (code "109") (name "unconnected-(H11-Pad4)") (class "Default")
      (node (ref "H11") (pin "4") (pinfunction "4_4") (pintype "input"))
    )
    (net (code "110") (name "unconnected-(H11-Pad5)") (class "Default")
      (node (ref "H11") (pin "5") (pinfunction "5_5") (pintype "input"))
    )
    (net (code "111") (name "unconnected-(H11-Pad6)") (class "Default")
      (node (ref "H11") (pin "6") (pinfunction "6_6") (pintype "input"))
    )
    (net (code "112") (name "unconnected-(SW1-PadMT1)") (class "Default")
      (node (ref "SW1") (pin "MT1") (pinfunction "MT1_MT1") (pintype "unspecified"))
    )
    (net (code "113") (name "unconnected-(SW1-PadMT2)") (class "Default")
      (node (ref "SW1") (pin "MT2") (pinfunction "MT2_MT2") (pintype "unspecified"))
    )
    (net (code "114") (name "unconnected-(U2-COM-Pad9)") (class "Default")
      (node (ref "U2") (pin "9") (pinfunction "COM_9") (pintype "unspecified"))
    )
    (net (code "115") (name "unconnected-(U5-COM-Pad9)") (class "Default")
      (node (ref "U5") (pin "9") (pinfunction "COM_9") (pintype "unspecified"))
    )
  )
)
